# LockDriver.net
KiCad netlist of a schematic drawn in EAGLE
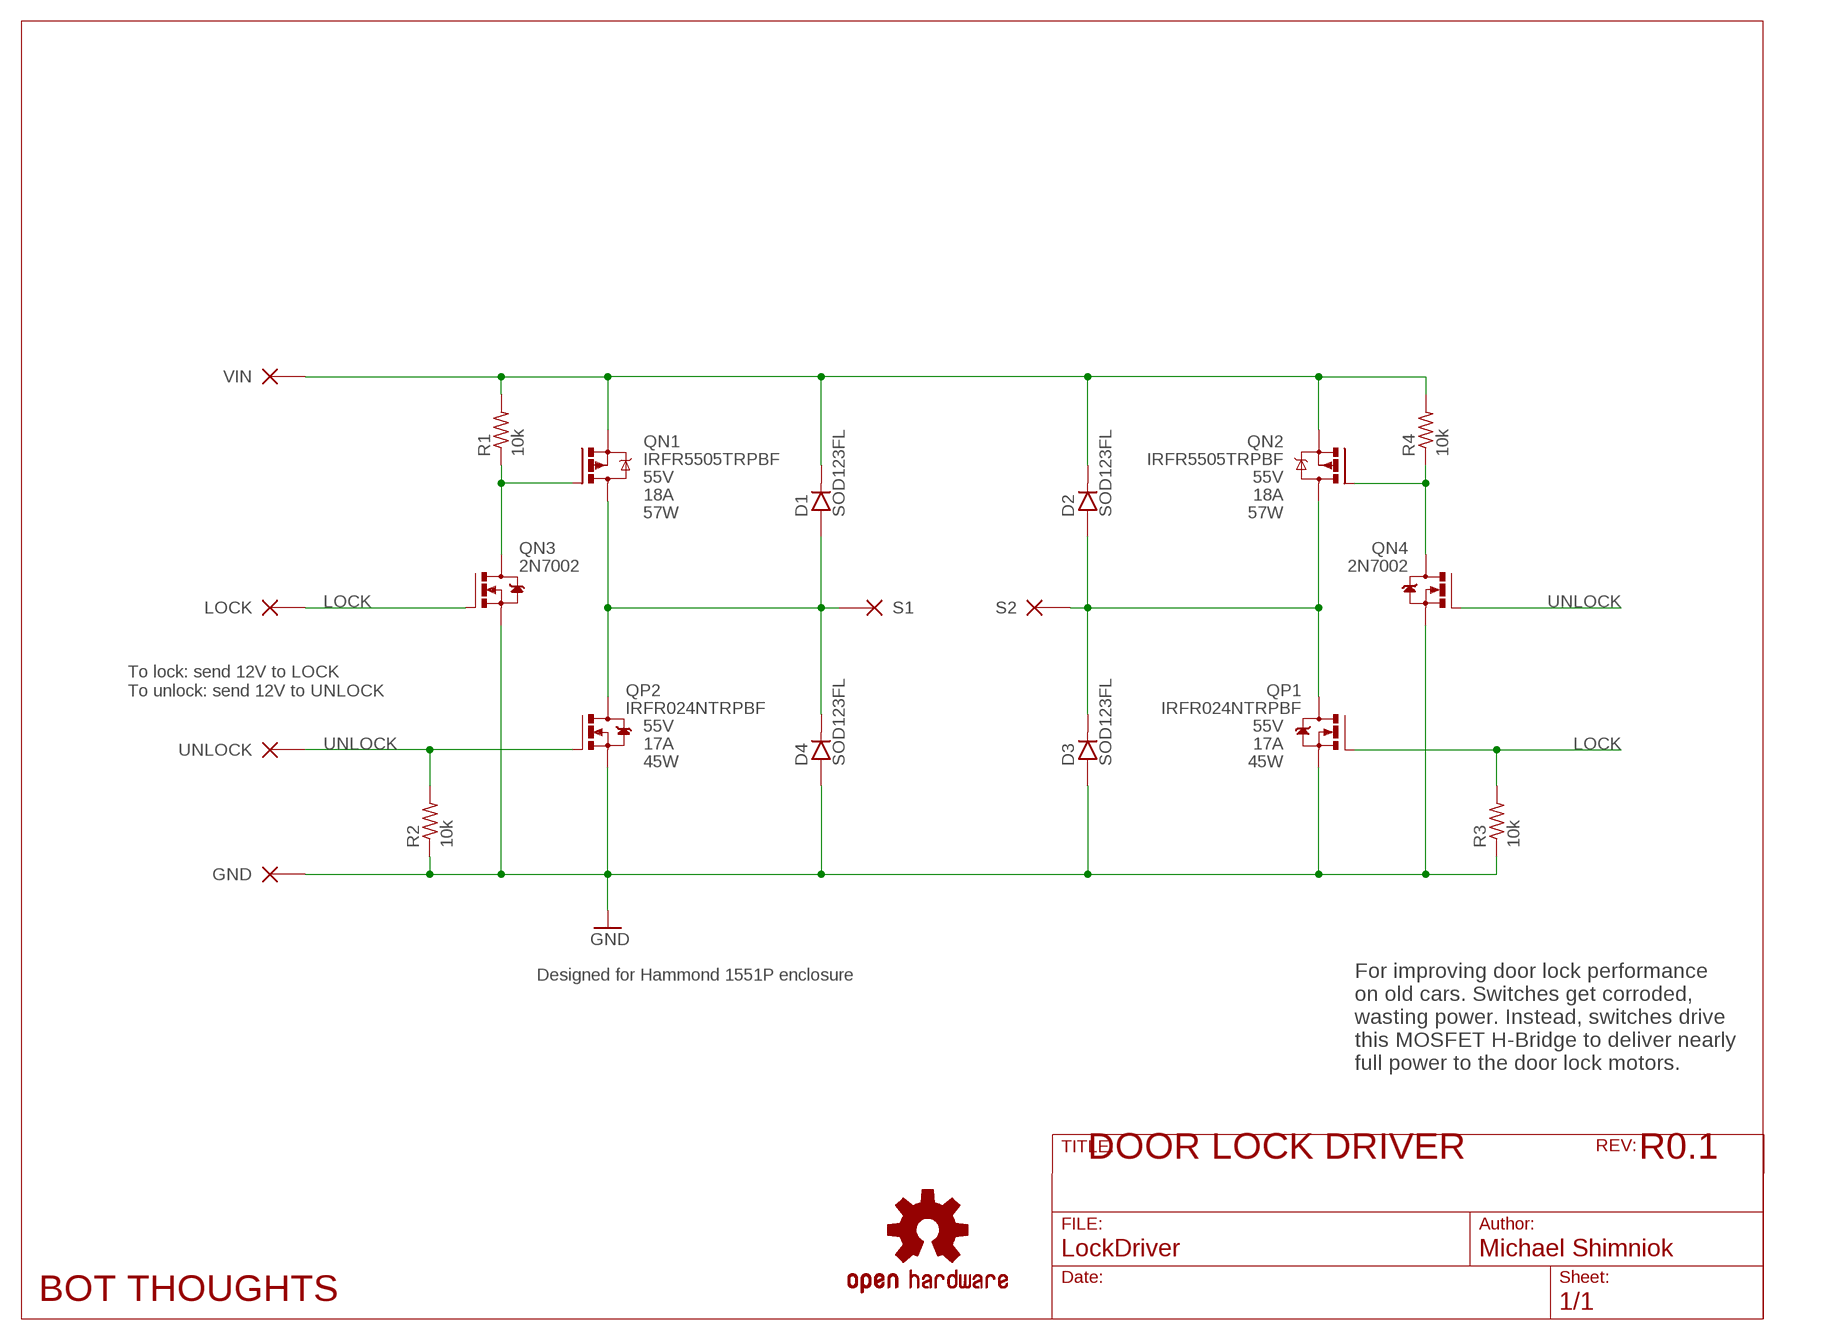
[diagram p0: schematic, sheet 1]

(export (version "E")
  (design (tool "Eeschema 10.0.6"))
  (components
    (comp (ref "D1")
      (value "SOD123FL")
      (footprint "eagle-import:SOD123FL")
      (libsource (lib "eagle-import") (part "DIODE_SOD123FL"))
    )
    (comp (ref "D2")
      (value "SOD123FL")
      (footprint "eagle-import:SOD123FL")
      (libsource (lib "eagle-import") (part "DIODE_SOD123FL"))
    )
    (comp (ref "D3")
      (value "SOD123FL")
      (footprint "eagle-import:SOD123FL")
      (libsource (lib "eagle-import") (part "DIODE_SOD123FL"))
    )
    (comp (ref "D4")
      (value "SOD123FL")
      (footprint "eagle-import:SOD123FL")
      (libsource (lib "eagle-import") (part "DIODE_SOD123FL"))
    )
    (comp (ref "LOGO1")
      (value "OSHW-LOGOS")
      (footprint "eagle-import:OSHW-LOGO-S")
      (libsource (lib "eagle-import") (part "OSHW-LOGOS"))
    )
    (comp (ref "QN1")
      (value "IRFR5505TRPBF")
      (footprint "eagle-import:TO252")
      (fields (field (name "CURRENT") "18A") (field (name "POWER") "57W") (field (name "VOLTAGE") "55V"))
      (libsource (lib "eagle-import") (part "MOSFET-PTO252"))
    )
    (comp (ref "QN2")
      (value "IRFR5505TRPBF")
      (footprint "eagle-import:TO252")
      (fields (field (name "CURRENT") "18A") (field (name "POWER") "57W") (field (name "VOLTAGE") "55V"))
      (libsource (lib "eagle-import") (part "MOSFET-PTO252"))
    )
    (comp (ref "QN3")
      (value "2N7002")
      (footprint "eagle-import:SOT-23")
      (libsource (lib "eagle-import") (part "MOSFET-N.SOT23"))
    )
    (comp (ref "QN4")
      (value "2N7002")
      (footprint "eagle-import:SOT-23")
      (libsource (lib "eagle-import") (part "MOSFET-N.SOT23"))
    )
    (comp (ref "QP1")
      (value "IRFR024NTRPBF")
      (footprint "eagle-import:TO252")
      (fields (field (name "CURRENT") "17A") (field (name "POWER") "45W") (field (name "VOLTAGE") "55V"))
      (libsource (lib "eagle-import") (part "MOSFET-NTO252"))
    )
    (comp (ref "QP2")
      (value "IRFR024NTRPBF")
      (footprint "eagle-import:TO252")
      (fields (field (name "CURRENT") "17A") (field (name "POWER") "45W") (field (name "VOLTAGE") "55V"))
      (libsource (lib "eagle-import") (part "MOSFET-NTO252"))
    )
    (comp (ref "R1")
      (value "10k")
      (footprint "eagle-import:R0603")
      (libsource (lib "eagle-import") (part "R-US_R0603"))
    )
    (comp (ref "R2")
      (value "10k")
      (footprint "eagle-import:R0603")
      (libsource (lib "eagle-import") (part "R-US_R0603"))
    )
    (comp (ref "R3")
      (value "10k")
      (footprint "eagle-import:R0603")
      (libsource (lib "eagle-import") (part "R-US_R0603"))
    )
    (comp (ref "R4")
      (value "10k")
      (footprint "eagle-import:R0603")
      (libsource (lib "eagle-import") (part "R-US_R0603"))
    )
    (comp (ref "U$2")
      (value "BOT-THOUGHTSLOGO_M")
      (footprint "eagle-import:BTLOGOM")
      (libsource (lib "eagle-import") (part "BOT-THOUGHTSLOGO_M"))
    )
    (comp (ref "X1")
      (value "S1")
      (footprint "eagle-import:PAD_14GA")
      (libsource (lib "eagle-import") (part "WIREPAD_14GA"))
    )
    (comp (ref "X2")
      (value "S2")
      (footprint "eagle-import:PAD_14GA")
      (libsource (lib "eagle-import") (part "WIREPAD_14GA"))
    )
    (comp (ref "X3")
      (value "VIN")
      (footprint "eagle-import:PAD_12GA")
      (libsource (lib "eagle-import") (part "WIREPAD_12GA"))
    )
    (comp (ref "X4")
      (value "GND")
      (footprint "eagle-import:PAD_12GA")
      (libsource (lib "eagle-import") (part "WIREPAD_12GA"))
    )
    (comp (ref "X5")
      (value "LOCK")
      (footprint "eagle-import:PAD_18GA")
      (libsource (lib "eagle-import") (part "WIREPAD_18GA"))
    )
    (comp (ref "X6")
      (value "UNLOCK")
      (footprint "eagle-import:PAD_18GA")
      (libsource (lib "eagle-import") (part "WIREPAD_18GA"))
    )
  )
  (nets
    (net (code "1") (name "/LOCK") (class "Default")
      (node (ref "QN3") (pin "1") (pinfunction "G_1") (pintype "passive"))
      (node (ref "QP1") (pin "1") (pinfunction "G_1") (pintype "passive"))
      (node (ref "R3") (pin "2") (pinfunction "2_2") (pintype "passive"))
      (node (ref "X5") (pin "P$1") (pinfunction "P_P$1") (pintype "bidirectional"))
    )
    (net (code "2") (name "/UNLOCK") (class "Default")
      (node (ref "QN4") (pin "1") (pinfunction "G_1") (pintype "passive"))
      (node (ref "QP2") (pin "1") (pinfunction "G_1") (pintype "passive"))
      (node (ref "R2") (pin "2") (pinfunction "2_2") (pintype "passive"))
      (node (ref "X6") (pin "P$1") (pinfunction "P_P$1") (pintype "bidirectional"))
    )
    (net (code "3") (name "GND") (class "Default")
      (node (ref "D3") (pin "A") (pinfunction "A_A") (pintype "passive"))
      (node (ref "D4") (pin "A") (pinfunction "A_A") (pintype "passive"))
      (node (ref "QN3") (pin "2") (pinfunction "S_2") (pintype "passive"))
      (node (ref "QN4") (pin "2") (pinfunction "S_2") (pintype "passive"))
      (node (ref "QP1") (pin "2") (pinfunction "S_2") (pintype "passive"))
      (node (ref "QP2") (pin "2") (pinfunction "S_2") (pintype "passive"))
      (node (ref "R2") (pin "1") (pinfunction "1_1") (pintype "passive"))
      (node (ref "R3") (pin "1") (pinfunction "1_1") (pintype "passive"))
      (node (ref "X4") (pin "P$1") (pinfunction "P_P$1") (pintype "bidirectional"))
    )
    (net (code "4") (name "Net-(QN1-D)") (class "Default")
      (node (ref "D1") (pin "A") (pinfunction "A_A") (pintype "passive"))
      (node (ref "D4") (pin "C") (pinfunction "C_C") (pintype "passive"))
      (node (ref "QN1") (pin "3") (pinfunction "D_3") (pintype "passive"))
      (node (ref "QP2") (pin "3") (pinfunction "D_3") (pintype "passive"))
      (node (ref "X1") (pin "P$1") (pinfunction "P_P$1") (pintype "bidirectional"))
    )
    (net (code "5") (name "Net-(QN1-G)") (class "Default")
      (node (ref "QN1") (pin "1") (pinfunction "G_1") (pintype "passive"))
      (node (ref "QN3") (pin "3") (pinfunction "D_3") (pintype "passive"))
      (node (ref "R1") (pin "1") (pinfunction "1_1") (pintype "passive"))
    )
    (net (code "6") (name "Net-(QN1-S)") (class "Default")
      (node (ref "D1") (pin "C") (pinfunction "C_C") (pintype "passive"))
      (node (ref "D2") (pin "C") (pinfunction "C_C") (pintype "passive"))
      (node (ref "QN1") (pin "2") (pinfunction "S_2") (pintype "passive"))
      (node (ref "QN2") (pin "2") (pinfunction "S_2") (pintype "passive"))
      (node (ref "R1") (pin "2") (pinfunction "2_2") (pintype "passive"))
      (node (ref "R4") (pin "2") (pinfunction "2_2") (pintype "passive"))
      (node (ref "X3") (pin "P$1") (pinfunction "P_P$1") (pintype "bidirectional"))
    )
    (net (code "7") (name "Net-(QN2-D)") (class "Default")
      (node (ref "D2") (pin "A") (pinfunction "A_A") (pintype "passive"))
      (node (ref "D3") (pin "C") (pinfunction "C_C") (pintype "passive"))
      (node (ref "QN2") (pin "3") (pinfunction "D_3") (pintype "passive"))
      (node (ref "QP1") (pin "3") (pinfunction "D_3") (pintype "passive"))
      (node (ref "X2") (pin "P$1") (pinfunction "P_P$1") (pintype "bidirectional"))
    )
    (net (code "8") (name "Net-(QN2-G)") (class "Default")
      (node (ref "QN2") (pin "1") (pinfunction "G_1") (pintype "passive"))
      (node (ref "QN4") (pin "3") (pinfunction "D_3") (pintype "passive"))
      (node (ref "R4") (pin "1") (pinfunction "1_1") (pintype "passive"))
    )
  )
)
